# Sheet1.net
KiCad netlist of a schematic drawn in Altium Designer
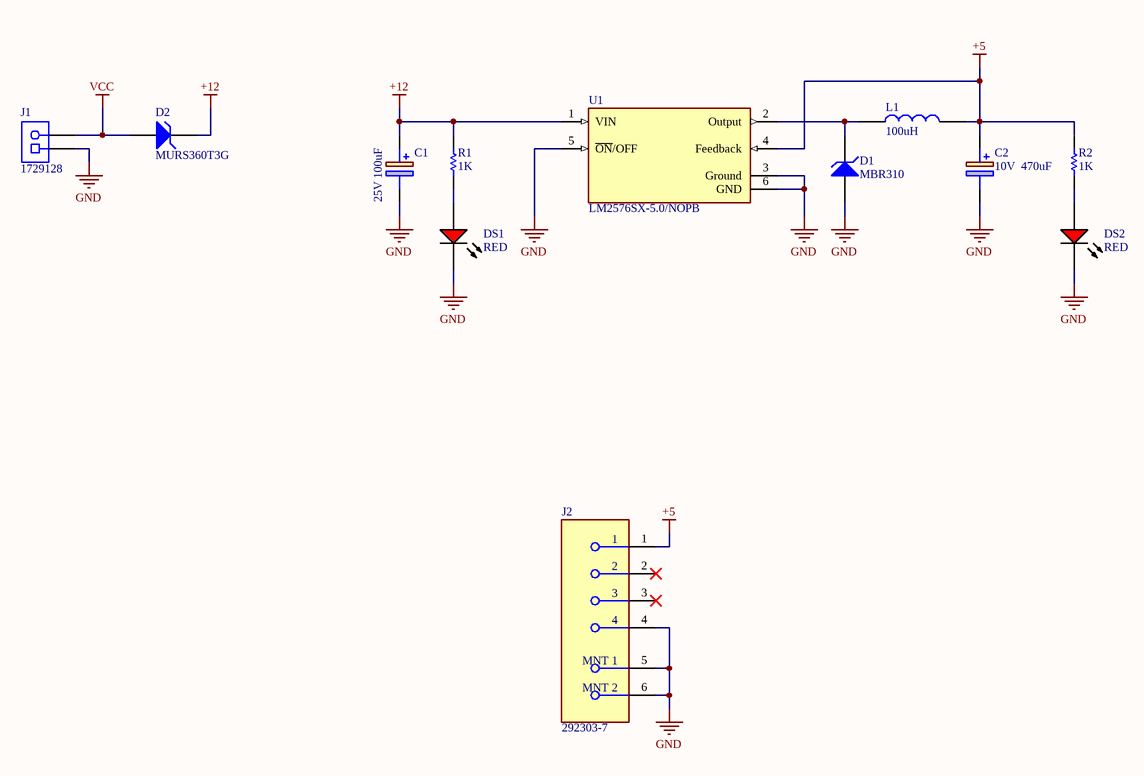
[diagram p0: Sheet1.SchDoc]

(export (version "E")
  (design (tool "Eeschema 10.0.6"))
  (components
    (comp (ref "C1")
      (value "25V 100uF")
      (footprint "EEHZA1E101XP")
      (description "BXJ25VC100MF80TP")
      (fields
        (field (name "MANUFACTURER_PART_NUMBER") "EEH-ZA1E101XP")
        (field (name "MOUSER PART NUMBER") "667-EEH-ZA1E101XP")
      )
      (libsource (lib "EEH-ZA1E101XP") (part "EEH-ZA1E101XP"))
    )
    (comp (ref "C2")
      (value "10V  470uF")
      (footprint "EEHZA1E101XP")
      (description "EEE-FTA471XAP")
      (fields
        (field (name "MANUFACTURER_PART_NUMBER") "EEH-ZA1E101XP")
        (field (name "MOUSER PART NUMBER") "667-EEH-ZA1E101XP")
      )
      (libsource (lib "EEH-ZA1E101XP") (part "EEH-ZA1E101XP"))
    )
    (comp (ref "D1")
      (value "MBR310")
      (footprint "LFUS-DO-214AB-2_V")
      (description "MB310_R1_00001")
      (fields (field (name "MANUFACTURER") "Littelfuse"))
      (libsource (lib "Altium Content Vault") (part "DZEN-AK-2"))
    )
    (comp (ref "D2")
      (value "MURS360T3G")
      (footprint "LFUS-DO-214AB-2_V")
      (fields (field (name "MANUFACTURER") "Littelfuse"))
      (libsource (lib "Altium Content Vault") (part "DZEN-AK-2"))
    )
    (comp (ref "DS1")
      (value "RED")
      (footprint "LUMX-SML-LX1206IC_V")
      (description "HL-PC-3216S9AC")
      (fields (field (name "MANUFACTURER") "Lumex") (field (name "PART NO") "SML-LX1206IC-TR"))
      (libsource (lib "Altium Content Vault") (part "LED-RED-AK-2"))
    )
    (comp (ref "DS2")
      (value "RED")
      (footprint "LUMX-SML-LX1206IC_V")
      (description "HL-PC-3216S9AC")
      (fields (field (name "MANUFACTURER") "Lumex") (field (name "PART NO") "SML-LX1206IC-TR"))
      (libsource (lib "Altium Content Vault") (part "LED-RED-AK-2"))
    )
    (comp (ref "J1")
      (value "1729128")
      (footprint "PHOE-1729128-2_V")
      (description "PCB Terminal Block, 13.5 A, 400 V, 2-Pin THD, RoHS, Bulk")
      (fields (field (name "MANUFACTURER") "Phoenix Contact"))
      (libsource (lib "Altium Content Vault") (part "CN-2P-F-R2"))
    )
    (comp (ref "J2")
      (value "292303-7")
      (footprint "FP-292303-7-MFG")
      (description "CONN RCPT USB2.0 TYPEA 4P SMD RA")
      (fields
        (field (name "OCTOPART") "https://octopart.com/292303-7-te+connectivity-42840369")
        (field (name "MANUFACTURER") "TE Connectivity")
      )
      (libsource (lib "Altium Content Vault") (part "79e6714efa0bb2f851c24b2688127c9"))
    )
    (comp (ref "L1")
      (value "100uH")
      (footprint "SRR1260101M")
      (description "SRI1209-101M")
      (fields
        (field (name "MANUFACTURER_PART_NUMBER") "SRR1260-101M")
        (field (name "MOUSER PART NUMBER") "652-SRR1260-101M")
      )
      (libsource (lib "SRR1260-101M") (part "SRR1260-101M"))
    )
    (comp (ref "R1")
      (value "1K")
      (footprint "RESC3216X70X50NL05T20")
      (description "1206S4F1001T5E")
      (fields (field (name "MANUFACTURER") "Panasonic") (field (name "PART NUMBER") "ERJ-8GEY0R00V"))
      (libsource (lib "Altium Content Vault") (part "RES"))
    )
    (comp (ref "R2")
      (value "1K")
      (footprint "RESC3216X70X50NL05T20")
      (description "1206S4F1001T5E")
      (fields (field (name "MANUFACTURER") "Panasonic") (field (name "PART NUMBER") "ERJ-8GEY0R00V"))
      (libsource (lib "Altium Content Vault") (part "RES"))
    )
    (comp (ref "U1")
      (value "LM2576SX-5.0/NOPB")
      (footprint "FP-KTT0005B-MFG")
      (description "IC REG BUCK 5V 3A TO263-5")
      (libsource (lib "Altium Content Vault") (part "f0883da41c58ceda5f27a37e32163a8"))
    )
  )
  (nets
    (net (code "1") (name "+5") (class "Default")
      (node (ref "C2") (pin "1") (pinfunction "+_1") (pintype "passive"))
      (node (ref "J2") (pin "1") (pinfunction "1_1") (pintype "passive"))
      (node (ref "L1") (pin "2") (pinfunction "2_2") (pintype "passive"))
      (node (ref "R2") (pin "2") (pinfunction "2_2") (pintype "passive"))
      (node (ref "U1") (pin "4") (pinfunction "Feedback_4") (pintype "input"))
    )
    (net (code "2") (name "+12") (class "Default")
      (node (ref "C1") (pin "1") (pinfunction "+_1") (pintype "passive"))
      (node (ref "D2") (pin "2") (pinfunction "K_2") (pintype "passive"))
      (node (ref "R1") (pin "2") (pinfunction "2_2") (pintype "passive"))
      (node (ref "U1") (pin "1") (pinfunction "VIN_1") (pintype "input"))
    )
    (net (code "3") (name "GND") (class "Default")
      (node (ref "C1") (pin "2") (pinfunction "-_2") (pintype "passive"))
      (node (ref "C2") (pin "2") (pinfunction "-_2") (pintype "passive"))
      (node (ref "D1") (pin "1") (pinfunction "A_1") (pintype "passive"))
      (node (ref "DS1") (pin "2") (pinfunction "K_2") (pintype "passive"))
      (node (ref "DS2") (pin "2") (pinfunction "K_2") (pintype "passive"))
      (node (ref "J1") (pin "1") (pinfunction "1_1") (pintype "passive"))
      (node (ref "J2") (pin "4") (pinfunction "4_4") (pintype "passive"))
      (node (ref "J2") (pin "5") (pinfunction "MNT_1_5") (pintype "passive"))
      (node (ref "J2") (pin "6") (pinfunction "MNT_2_6") (pintype "passive"))
      (node (ref "U1") (pin "3") (pinfunction "Ground_3") (pintype "power_in"))
      (node (ref "U1") (pin "5") (pinfunction "~{ON}/OFF_5") (pintype "input"))
      (node (ref "U1") (pin "6") (pinfunction "GND_6") (pintype "power_in"))
    )
    (net (code "4") (name "Net-(D1-K)") (class "Default")
      (node (ref "D1") (pin "2") (pinfunction "K_2") (pintype "passive"))
      (node (ref "L1") (pin "1") (pinfunction "1_1") (pintype "passive"))
      (node (ref "U1") (pin "2") (pinfunction "Output_2") (pintype "output"))
    )
    (net (code "5") (name "Net-(DS1-A)") (class "Default")
      (node (ref "DS1") (pin "1") (pinfunction "A_1") (pintype "passive"))
      (node (ref "R1") (pin "1") (pinfunction "1_1") (pintype "passive"))
    )
    (net (code "6") (name "Net-(DS2-A)") (class "Default")
      (node (ref "DS2") (pin "1") (pinfunction "A_1") (pintype "passive"))
      (node (ref "R2") (pin "1") (pinfunction "1_1") (pintype "passive"))
    )
    (net (code "7") (name "VCC") (class "Default")
      (node (ref "D2") (pin "1") (pinfunction "A_1") (pintype "passive"))
      (node (ref "J1") (pin "2") (pinfunction "2_2") (pintype "passive"))
    )
    (net (code "8") (name "unconnected-(J2-Pad2)") (class "Default")
      (node (ref "J2") (pin "2") (pinfunction "2_2") (pintype "passive+no_connect"))
    )
    (net (code "9") (name "unconnected-(J2-Pad3)") (class "Default")
      (node (ref "J2") (pin "3") (pinfunction "3_3") (pintype "passive+no_connect"))
    )
  )
)
